# IO.net
KiCad netlist of a schematic drawn in Altium Designer
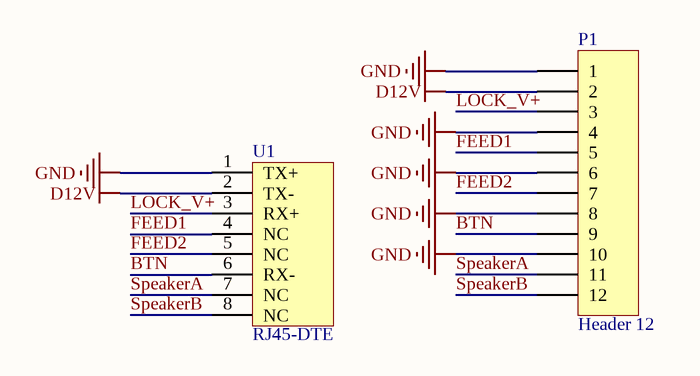
[diagram p0: IO.SchDoc]

(export (version "E")
  (design (tool "Eeschema 10.0.6"))
  (components
    (comp (ref "P1")
      (value "Header 12")
      (footprint "KF141R-2.54-12")
      (description "Header, 12-Pin")
      (fields (field (name "PUBLISHER") "Altium Limited"))
      (libsource (lib "lib_AD") (part "Header 12"))
    )
    (comp (ref "U1") (value "RJ45-DTE") (footprint "RJ45") (libsource (lib "lib_AD") (part "RJ45-DTE")))
  )
  (nets
    (net (code "1") (name "/BTN") (class "Default")
      (node (ref "P1") (pin "9") (pinfunction "9_9") (pintype "passive"))
      (node (ref "U1") (pin "6") (pinfunction "RX-_6") (pintype "passive"))
    )
    (net (code "2") (name "/FEED1") (class "Default")
      (node (ref "P1") (pin "5") (pinfunction "5_5") (pintype "passive"))
      (node (ref "U1") (pin "4") (pinfunction "NC_4") (pintype "passive"))
    )
    (net (code "3") (name "/FEED2") (class "Default")
      (node (ref "P1") (pin "7") (pinfunction "7_7") (pintype "passive"))
      (node (ref "U1") (pin "5") (pinfunction "NC_5") (pintype "passive"))
    )
    (net (code "4") (name "/LOCK_V+") (class "Default")
      (node (ref "P1") (pin "3") (pinfunction "3_3") (pintype "passive"))
      (node (ref "U1") (pin "3") (pinfunction "RX+_3") (pintype "passive"))
    )
    (net (code "5") (name "/SpeakerA") (class "Default")
      (node (ref "P1") (pin "11") (pinfunction "11_11") (pintype "passive"))
      (node (ref "U1") (pin "7") (pinfunction "NC_7") (pintype "passive"))
    )
    (net (code "6") (name "/SpeakerB") (class "Default")
      (node (ref "P1") (pin "12") (pinfunction "12_12") (pintype "passive"))
      (node (ref "U1") (pin "8") (pinfunction "NC_8") (pintype "passive"))
    )
    (net (code "7") (name "D12V") (class "Default")
      (node (ref "P1") (pin "2") (pinfunction "2_2") (pintype "passive"))
      (node (ref "U1") (pin "2") (pinfunction "TX-_2") (pintype "passive"))
    )
    (net (code "8") (name "GND") (class "Default")
      (node (ref "P1") (pin "1") (pinfunction "1_1") (pintype "passive"))
      (node (ref "P1") (pin "10") (pinfunction "10_10") (pintype "passive"))
      (node (ref "P1") (pin "4") (pinfunction "4_4") (pintype "passive"))
      (node (ref "P1") (pin "6") (pinfunction "6_6") (pintype "passive"))
      (node (ref "P1") (pin "8") (pinfunction "8_8") (pintype "passive"))
      (node (ref "U1") (pin "1") (pinfunction "TX+_1") (pintype "passive"))
    )
  )
)
